# Sheet1.net
KiCad netlist of a schematic drawn in Altium Designer
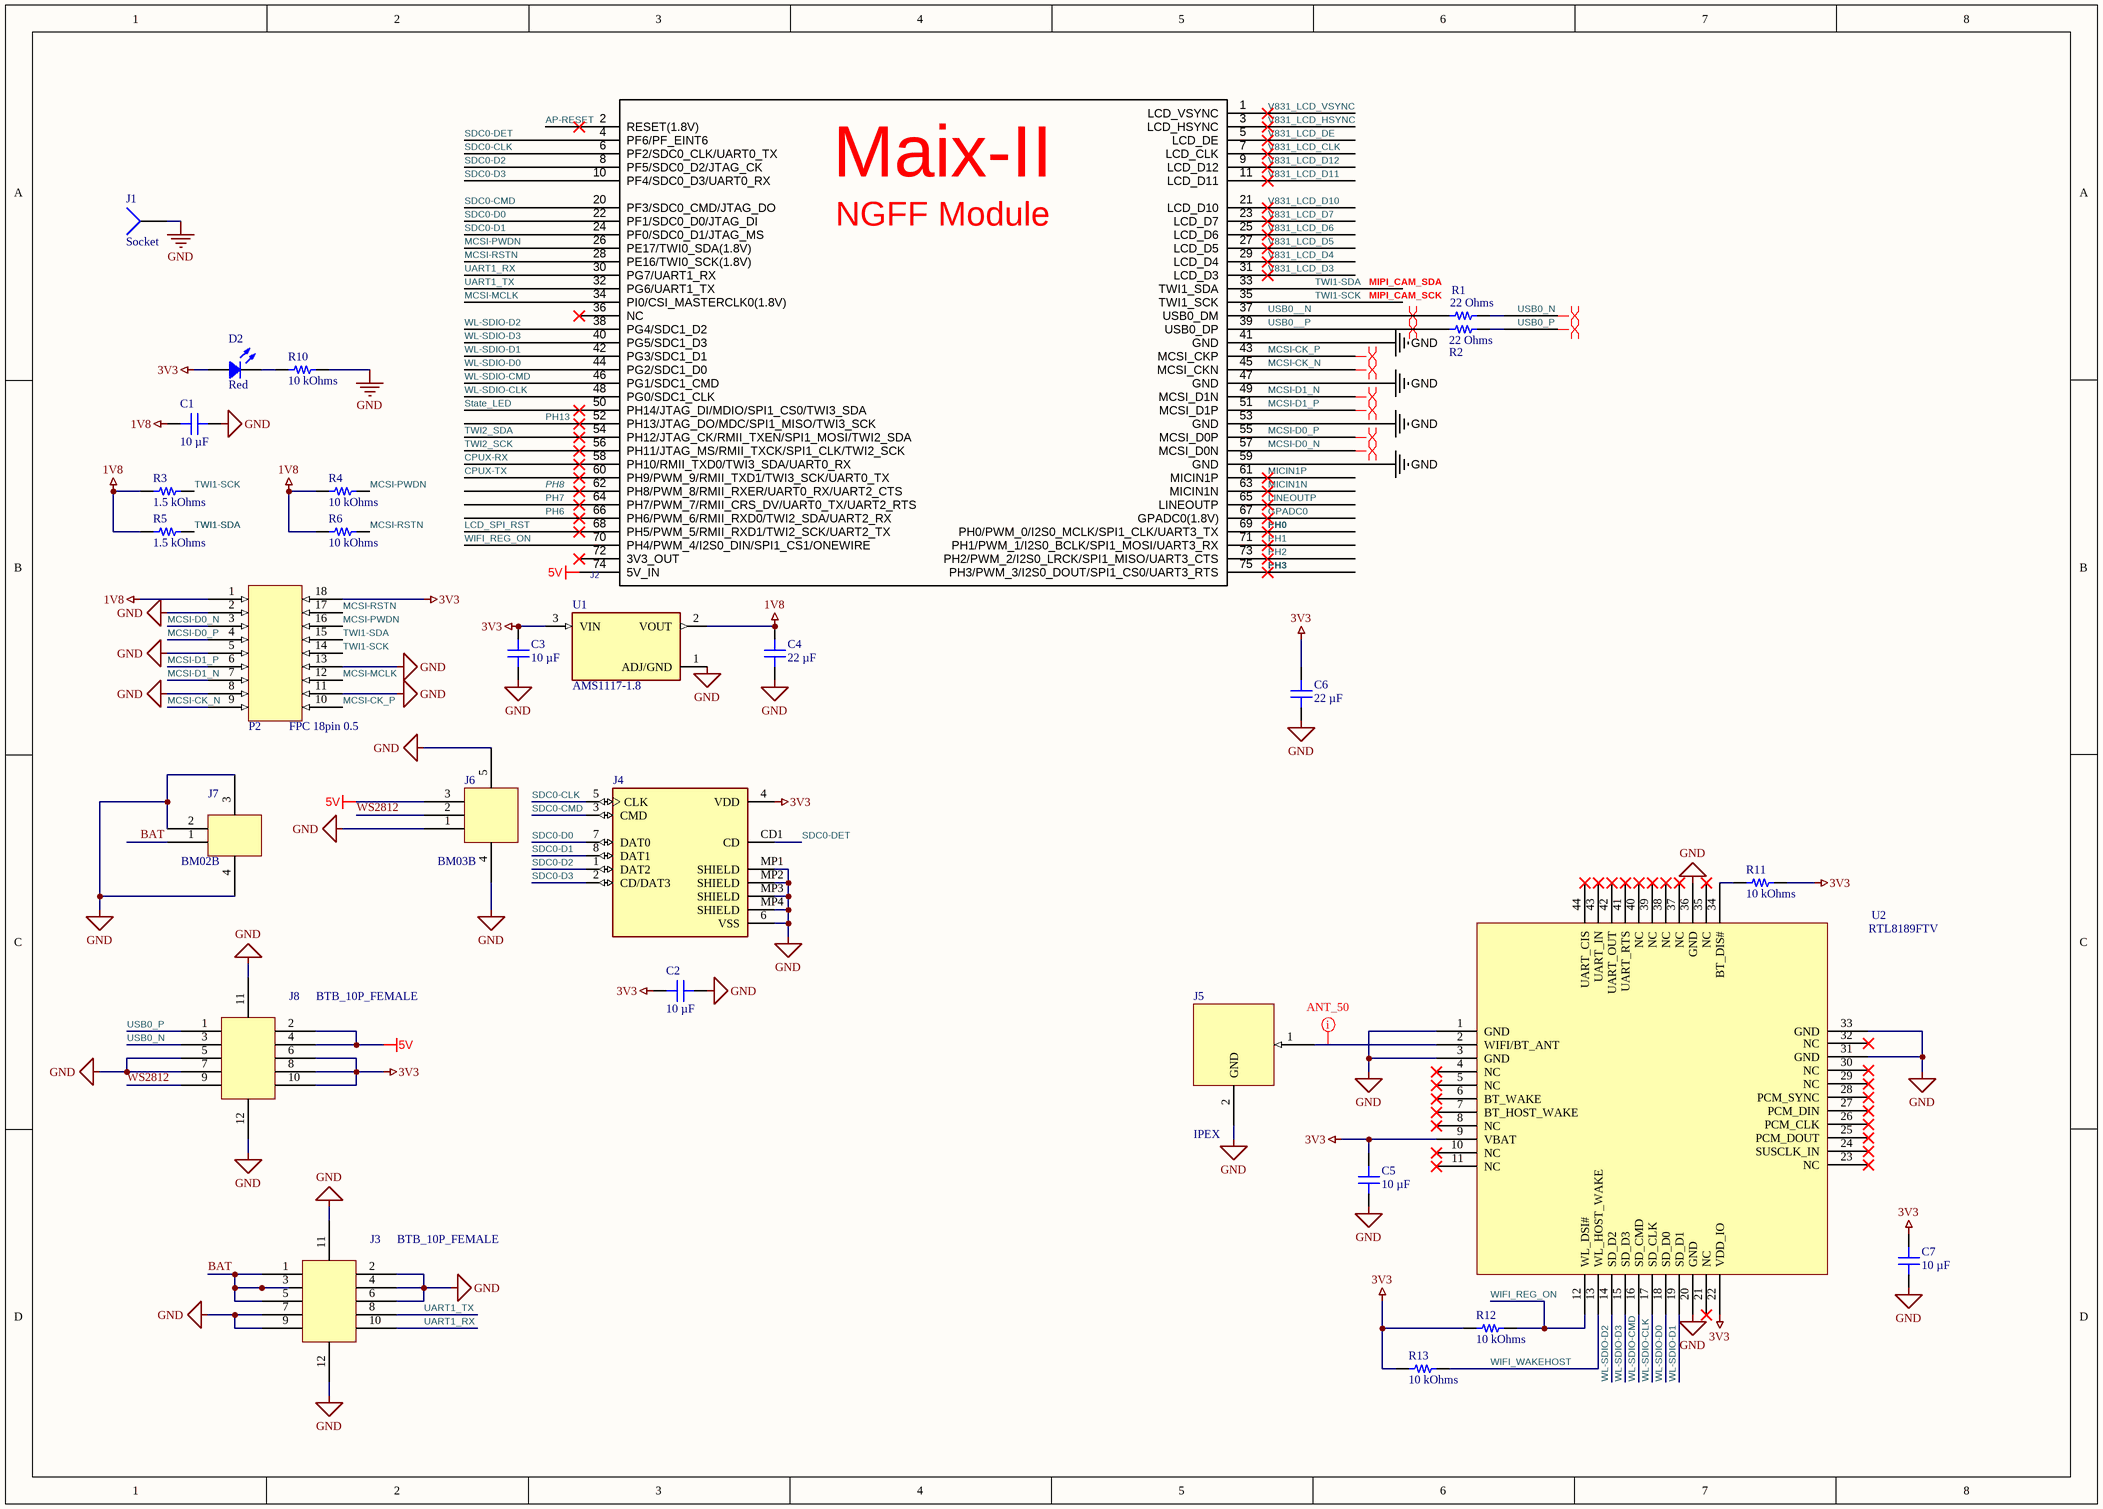
[diagram p0: Sheet1.SchDoc]

(export (version "E")
  (design (tool "Eeschema 10.0.6"))
  (components
    (comp (ref "C1")
      (value "10 µF")
      (footprint "CAP 0402_1005")
      (description "CAP CER 10UF 2.5V X5R 0402")
      (fields
        (field (name "PART NUMBER") "GRM155R60E106ME16D")
        (field (name "MANUFACTURER") "Murata Electronics")
      )
      (libsource (lib "Celestial Altium Library - altium_library") (part "Capacitor"))
    )
    (comp (ref "C2")
      (value "10 µF")
      (footprint "CAP 0402_1005")
      (description "CAP CER 10UF 2.5V X5R 0402")
      (fields
        (field (name "PART NUMBER") "GRM155R60E106ME16D")
        (field (name "MANUFACTURER") "Murata Electronics")
      )
      (libsource (lib "Celestial Altium Library - altium_library") (part "Capacitor"))
    )
    (comp (ref "C3")
      (value "10 µF")
      (footprint "CAP 0402_1005")
      (description "CAP CER 10UF 2.5V X5R 0402")
      (fields
        (field (name "PART NUMBER") "GRM155R60E106ME16D")
        (field (name "MANUFACTURER") "Murata Electronics")
      )
      (libsource (lib "Celestial Altium Library - altium_library") (part "Capacitor"))
    )
    (comp (ref "C4")
      (value "22 µF")
      (footprint "CAP_TAN_A1206")
      (description "CAP CER 10UF 2.5V X5R 0402")
      (fields
        (field (name "PART NUMBER") "GRM155R60E106ME16D")
        (field (name "MANUFACTURER") "Murata Electronics")
      )
      (libsource (lib "Celestial Altium Library - altium_library") (part "Capacitor"))
    )
    (comp (ref "C5")
      (value "10 µF")
      (footprint "CAP 0402_1005")
      (description "CAP CER 10UF 2.5V X5R 0402")
      (fields
        (field (name "PART NUMBER") "GRM155R60E106ME16D")
        (field (name "MANUFACTURER") "Murata Electronics")
      )
      (libsource (lib "Celestial Altium Library - altium_library") (part "Capacitor"))
    )
    (comp (ref "C6")
      (value "22 µF")
      (footprint "CAP_TAN_A1206")
      (description "CAP CER 10UF 2.5V X5R 0402")
      (fields
        (field (name "PART NUMBER") "GRM155R60E106ME16D")
        (field (name "MANUFACTURER") "Murata Electronics")
      )
      (libsource (lib "Celestial Altium Library - altium_library") (part "Capacitor"))
    )
    (comp (ref "C7")
      (value "10 µF")
      (footprint "CAP 0402_1005")
      (description "CAP CER 10UF 2.5V X5R 0402")
      (fields
        (field (name "PART NUMBER") "GRM155R60E106ME16D")
        (field (name "MANUFACTURER") "Murata Electronics")
      )
      (libsource (lib "Celestial Altium Library - altium_library") (part "Capacitor"))
    )
    (comp (ref "D2")
      (value "Red")
      (footprint "LED_0603_RED")
      (description "0402 LED RED, CLEAR LENS, 330MCD")
      (fields (field (name "PART NUMBER") "QBLP595-R-2897") (field (name "MANUFACTURER") "QT Brightek (QTB)"))
      (libsource (lib "Celestial Altium Library - altium_library") (part "LED"))
    )
    (comp (ref "J1")
      (value "Socket")
      (footprint "M.2 SMT-FEMALE - FULL")
      (fields (field (name "PUBLISHER") "Altium Limited"))
      (libsource (lib "Miscellaneous Connectors") (part "Socket"))
    )
    (comp (ref "J2")
      (value "NGFF-67P_B-KEY座子 4.2H高")
      (footprint "M2-67P0R50_B_FEMALE")
      (libsource (lib "V831_Dock_3060") (part "NGFF-67P_B-MALE"))
    )
    (comp (ref "J3")
      (value "BTB_10P_FEMALE")
      (footprint "BTB_10P_FEMALE")
      (libsource (lib "cocube_maix") (part "BTB_10P_FEMALE"))
    )
    (comp (ref "J4")
      (value "TF-01A")
      (footprint "TF-01A")
      (fields (field (name "MF") "{'manufacturer': u'HRO Electronics Co., Ltd.'}"))
      (libsource (lib "SnapEDA_Library") (part "TF-01A"))
    )
    (comp (ref "J5") (value "IPEX") (footprint "IPEX") (libsource (lib "cocube_maix") (part "IPEX")))
    (comp (ref "J6") (value "BM03B") (footprint "BM03B") (libsource (lib "cocube_maix") (part "BM03B")))
    (comp (ref "J7") (value "BM02B") (footprint "BM02B") (libsource (lib "cocube_maix") (part "BM02B")))
    (comp (ref "J8")
      (value "BTB_10P_FEMALE")
      (footprint "BTB_10P_FEMALE")
      (libsource (lib "cocube_maix") (part "BTB_10P_FEMALE"))
    )
    (comp (ref "P2")
      (value "FPC 18pin 0.5")
      (footprint "FPC 18PIN STAND")
      (libsource (lib "maix_2") (part "FPC 18pin 0.5"))
    )
    (comp (ref "R1")
      (value "22 Ohms")
      (footprint "RES 0402_1005")
      (description "RES 22 OHM 1% 1/8W 0402")
      (fields (field (name "PART NUMBER") "SR0402FR-7W22RL") (field (name "MANUFACTURER") "Yageo"))
      (libsource (lib "Celestial Altium Library - altium_library") (part "Resistor"))
    )
    (comp (ref "R2")
      (value "22 Ohms")
      (footprint "RES 0402_1005")
      (description "RES 22 OHM 1% 1/8W 0402")
      (fields (field (name "PART NUMBER") "SR0402FR-7W22RL") (field (name "MANUFACTURER") "Yageo"))
      (libsource (lib "Celestial Altium Library - altium_library") (part "Resistor"))
    )
    (comp (ref "R3")
      (value "1.5 kOhms")
      (footprint "RES 0402_1005")
      (description "PTN0402 10PPM 1.5K 0.1% S T1 E1")
      (fields
        (field (name "PART NUMBER") "PTN0402Y1501BST1")
        (field (name "MANUFACTURER") "Vishay Dale Thin Film")
      )
      (libsource (lib "Celestial Altium Library - altium_library") (part "Resistor"))
    )
    (comp (ref "R4")
      (value "10 kOhms")
      (footprint "RES 0402_1005")
      (description "P2TC0402 2PPM/C 10K 0,01% N TA")
      (fields
        (field (name "PART NUMBER") "P2TC0402D1002LNTA")
        (field (name "MANUFACTURER") "Vishay Sfernice")
      )
      (libsource (lib "Celestial Altium Library - altium_library") (part "Resistor"))
    )
    (comp (ref "R5")
      (value "1.5 kOhms")
      (footprint "RES 0402_1005")
      (description "PTN0402 10PPM 1.5K 0.1% S T1 E1")
      (fields
        (field (name "PART NUMBER") "PTN0402Y1501BST1")
        (field (name "MANUFACTURER") "Vishay Dale Thin Film")
      )
      (libsource (lib "Celestial Altium Library - altium_library") (part "Resistor"))
    )
    (comp (ref "R6")
      (value "10 kOhms")
      (footprint "RES 0402_1005")
      (description "P2TC0402 2PPM/C 10K 0,01% N TA")
      (fields
        (field (name "PART NUMBER") "P2TC0402D1002LNTA")
        (field (name "MANUFACTURER") "Vishay Sfernice")
      )
      (libsource (lib "Celestial Altium Library - altium_library") (part "Resistor"))
    )
    (comp (ref "R10")
      (value "10 kOhms")
      (footprint "RES 0402_1005")
      (description "RES 10K OHM 0.1% 1/10W 0402")
      (fields
        (field (name "PART NUMBER") "RP73PF1E10KBTD")
        (field (name "MANUFACTURER") "TE Connectivity Passive Product")
      )
      (libsource (lib "Celestial Altium Library - altium_library") (part "Resistor"))
    )
    (comp (ref "R11")
      (value "10 kOhms")
      (footprint "RES 0402_1005")
      (description "P2TC0402 2PPM/C 10K 0,01% N TA")
      (fields
        (field (name "PART NUMBER") "P2TC0402D1002LNTA")
        (field (name "MANUFACTURER") "Vishay Sfernice")
      )
      (libsource (lib "Celestial Altium Library - altium_library") (part "Resistor"))
    )
    (comp (ref "R12")
      (value "10 kOhms")
      (footprint "RES 0402_1005")
      (description "P2TC0402 2PPM/C 10K 0,01% N TA")
      (fields
        (field (name "PART NUMBER") "P2TC0402D1002LNTA")
        (field (name "MANUFACTURER") "Vishay Sfernice")
      )
      (libsource (lib "Celestial Altium Library - altium_library") (part "Resistor"))
    )
    (comp (ref "R13")
      (value "10 kOhms")
      (footprint "RES 0402_1005")
      (description "P2TC0402 2PPM/C 10K 0,01% N TA")
      (fields
        (field (name "PART NUMBER") "P2TC0402D1002LNTA")
        (field (name "MANUFACTURER") "Vishay Sfernice")
      )
      (libsource (lib "Celestial Altium Library - altium_library") (part "Resistor"))
    )
    (comp (ref "U1")
      (value "AMS1117-1.8")
      (footprint "SOT89-3")
      (description "Sot223/Pkg 1-Amp 5-Volt Low Drop Out Voltage Regulatator")
      (fields
        (field (name "MP") "AMS1117")
        (field (name "MF") "{'manufacturer': u'Advanced Monolithic Systems'}")
      )
      (libsource (lib "maix_2") (part "AMS1117"))
    )
    (comp (ref "U2")
      (value "RTL8189FTV")
      (footprint "FT89FMST13")
      (libsource (lib "cocube_maix") (part "RTL8189FTV"))
    )
  )
  (nets
    (net (code "1") (name "/AP-RESET") (class "Default")
      (node (ref "J2") (pin "2") (pinfunction "RESET(1.8V)_2") (pintype "passive+no_connect"))
    )
    (net (code "2") (name "/BAT") (class "Default")
      (node (ref "J3") (pin "1") (pintype "passive"))
      (node (ref "J3") (pin "3") (pintype "passive"))
      (node (ref "J3") (pin "5") (pintype "passive"))
      (node (ref "J7") (pin "1") (pintype "passive"))
    )
    (net (code "3") (name "/CPUX-RX") (class "Default")
      (node (ref "J2") (pin "58") (pinfunction "PH10/RMII_TXD0/TWI3_SDA/UART0_RX_58") (pintype "passive+no_connect"))
    )
    (net (code "4") (name "/CPUX-TX") (class "Default")
      (node (ref "J2") (pin "60") (pinfunction "PH9/PWM_9/RMII_TXD1/TWI3_SCK/UART0_TX_60") (pintype "passive+no_connect"))
    )
    (net (code "5") (name "/GPADC0") (class "Default")
      (node (ref "J2") (pin "67") (pinfunction "GPADC0(1.8V)_67") (pintype "passive+no_connect"))
    )
    (net (code "6") (name "/LCD_SPI_RST") (class "Default")
      (node (ref "J2") (pin "68") (pinfunction "PH5/PWM_5/RMII_RXD1/TWI2_SCK/UART2_TX_68") (pintype "passive+no_connect"))
    )
    (net (code "7") (name "/LINEOUTP") (class "Default")
      (node (ref "J2") (pin "65") (pinfunction "LINEOUTP_65") (pintype "passive+no_connect"))
    )
    (net (code "8") (name "/MCSI-CK_N") (class "Default")
      (node (ref "J2") (pin "45") (pinfunction "MCSI_CKN_45") (pintype "passive"))
      (node (ref "P2") (pin "9") (pintype "input"))
    )
    (net (code "9") (name "/MCSI-CK_P") (class "Default")
      (node (ref "J2") (pin "43") (pinfunction "MCSI_CKP_43") (pintype "passive"))
      (node (ref "P2") (pin "10") (pintype "input"))
    )
    (net (code "10") (name "/MCSI-D0_N") (class "Default")
      (node (ref "J2") (pin "57") (pinfunction "MCSI_D0N_57") (pintype "passive"))
      (node (ref "P2") (pin "3") (pintype "input"))
    )
    (net (code "11") (name "/MCSI-D0_P") (class "Default")
      (node (ref "J2") (pin "55") (pinfunction "MCSI_D0P_55") (pintype "passive"))
      (node (ref "P2") (pin "4") (pintype "input"))
    )
    (net (code "12") (name "/MCSI-D1_N") (class "Default")
      (node (ref "J2") (pin "49") (pinfunction "MCSI_D1N_49") (pintype "passive"))
      (node (ref "P2") (pin "7") (pintype "input"))
    )
    (net (code "13") (name "/MCSI-D1_P") (class "Default")
      (node (ref "J2") (pin "51") (pinfunction "MCSI_D1P_51") (pintype "passive"))
      (node (ref "P2") (pin "6") (pintype "input"))
    )
    (net (code "14") (name "/MCSI-MCLK") (class "Default")
      (node (ref "J2") (pin "34") (pinfunction "PI0/CSI_MASTERCLK0(1.8V)_34") (pintype "passive"))
      (node (ref "P2") (pin "12") (pintype "input"))
    )
    (net (code "15") (name "/MCSI-PWDN") (class "Default")
      (node (ref "J2") (pin "26") (pinfunction "PE17/TWI0_SDA(1.8V)_26") (pintype "passive"))
      (node (ref "P2") (pin "16") (pintype "input"))
      (node (ref "R4") (pin "2") (pinfunction "2_2") (pintype "passive"))
    )
    (net (code "16") (name "/MCSI-RSTN") (class "Default")
      (node (ref "J2") (pin "28") (pinfunction "PE16/TWI0_SCK(1.8V)_28") (pintype "passive"))
      (node (ref "P2") (pin "17") (pintype "input"))
      (node (ref "R6") (pin "2") (pinfunction "2_2") (pintype "passive"))
    )
    (net (code "17") (name "/MICIN1N") (class "Default")
      (node (ref "J2") (pin "63") (pinfunction "MICIN1N_63") (pintype "passive+no_connect"))
    )
    (net (code "18") (name "/MICIN1P") (class "Default")
      (node (ref "J2") (pin "61") (pinfunction "MICIN1P_61") (pintype "passive+no_connect"))
    )
    (net (code "19") (name "/PH0") (class "Default")
      (node (ref "J2") (pin "69") (pinfunction "PH0/PWM_0/I2S0_MCLK/SPI1_CLK/UART3_TX_69") (pintype "passive+no_connect"))
    )
    (net (code "20") (name "/PH1") (class "Default")
      (node (ref "J2") (pin "71") (pinfunction "PH1/PWM_1/I2S0_BCLK/SPI1_MOSI/UART3_RX_71") (pintype "passive+no_connect"))
    )
    (net (code "21") (name "/PH2") (class "Default")
      (node (ref "J2") (pin "73") (pinfunction "PH2/PWM_2/I2S0_LRCK/SPI1_MISO/UART3_CTS_73") (pintype "passive+no_connect"))
    )
    (net (code "22") (name "/PH3") (class "Default")
      (node (ref "J2") (pin "75") (pinfunction "PH3/PWM_3/I2S0_DOUT/SPI1_CS0/UART3_RTS_75") (pintype "passive+no_connect"))
    )
    (net (code "23") (name "/PH6") (class "Default")
      (node (ref "J2") (pin "66") (pinfunction "PH6/PWM_6/RMII_RXD0/TWI2_SDA/UART2_RX_66") (pintype "passive+no_connect"))
    )
    (net (code "24") (name "/PH7") (class "Default")
      (node (ref "J2") (pin "64") (pinfunction "PH7/PWM_7/RMII_CRS_DV/UART0_TX/UART2_RTS_64") (pintype "passive+no_connect"))
    )
    (net (code "25") (name "/PH8") (class "Default")
      (node (ref "J2") (pin "62") (pinfunction "PH8/PWM_8/RMII_RXER/UART0_RX/UART2_CTS_62") (pintype "passive+no_connect"))
    )
    (net (code "26") (name "/PH13") (class "Default")
      (node (ref "J2") (pin "52") (pinfunction "PH13/JTAG_DO/MDC/SPI1_MISO/TWI3_SCK_52") (pintype "passive+no_connect"))
    )
    (net (code "27") (name "/SDC0-CLK") (class "Default")
      (node (ref "J2") (pin "6") (pinfunction "PF2/SDC0_CLK/UART0_TX_6") (pintype "passive"))
      (node (ref "J4") (pin "5") (pinfunction "CLK_5") (pintype "bidirectional"))
    )
    (net (code "28") (name "/SDC0-CMD") (class "Default")
      (node (ref "J2") (pin "20") (pinfunction "PF3/SDC0_CMD/JTAG_DO_20") (pintype "passive"))
      (node (ref "J4") (pin "3") (pinfunction "CMD_3") (pintype "bidirectional"))
    )
    (net (code "29") (name "/SDC0-D0") (class "Default")
      (node (ref "J2") (pin "22") (pinfunction "PF1/SDC0_D0/JTAG_DI_22") (pintype "passive"))
      (node (ref "J4") (pin "7") (pinfunction "DAT0_7") (pintype "bidirectional"))
    )
    (net (code "30") (name "/SDC0-D1") (class "Default")
      (node (ref "J2") (pin "24") (pinfunction "PF0/SDC0_D1/JTAG_MS_24") (pintype "passive"))
      (node (ref "J4") (pin "8") (pinfunction "DAT1_8") (pintype "bidirectional"))
    )
    (net (code "31") (name "/SDC0-D2") (class "Default")
      (node (ref "J2") (pin "8") (pinfunction "PF5/SDC0_D2/JTAG_CK_8") (pintype "passive"))
      (node (ref "J4") (pin "1") (pinfunction "DAT2_1") (pintype "bidirectional"))
    )
    (net (code "32") (name "/SDC0-D3") (class "Default")
      (node (ref "J2") (pin "10") (pinfunction "PF4/SDC0_D3/UART0_RX_10") (pintype "passive"))
      (node (ref "J4") (pin "2") (pinfunction "CD/DAT3_2") (pintype "bidirectional"))
    )
    (net (code "33") (name "/SDC0-DET") (class "Default")
      (node (ref "J2") (pin "4") (pinfunction "PF6/PF_EINT6_4") (pintype "passive"))
      (node (ref "J4") (pin "CD1") (pinfunction "CD_CD1") (pintype "passive"))
    )
    (net (code "34") (name "/State_LED") (class "Default")
      (node (ref "J2") (pin "50") (pinfunction "PH14/JTAG_DI/MDIO/SPI1_CS0/TWI3_SDA_50") (pintype "passive+no_connect"))
    )
    (net (code "35") (name "/TWI1-SCK") (class "Default")
      (node (ref "J2") (pin "35") (pinfunction "TWI1_SCK_35") (pintype "passive"))
      (node (ref "P2") (pin "14") (pintype "input"))
      (node (ref "R3") (pin "2") (pinfunction "2_2") (pintype "passive"))
    )
    (net (code "36") (name "/TWI1-SDA") (class "Default")
      (node (ref "J2") (pin "33") (pinfunction "TWI1_SDA_33") (pintype "passive"))
      (node (ref "P2") (pin "15") (pintype "input"))
      (node (ref "R5") (pin "2") (pinfunction "2_2") (pintype "passive"))
    )
    (net (code "37") (name "/TWI2_SCK") (class "Default")
      (node (ref "J2") (pin "56") (pinfunction "PH11/JTAG_MS/RMII_TXCK/SPI1_CLK/TWI2_SCK_56") (pintype "passive+no_connect"))
    )
    (net (code "38") (name "/TWI2_SDA") (class "Default")
      (node (ref "J2") (pin "54") (pinfunction "PH12/JTAG_CK/RMII_TXEN/SPI1_MOSI/TWI2_SDA_54") (pintype "passive+no_connect"))
    )
    (net (code "39") (name "/UART1_RX") (class "Default")
      (node (ref "J2") (pin "30") (pinfunction "PG7/UART1_RX_30") (pintype "passive"))
      (node (ref "J3") (pin "10") (pintype "passive"))
    )
    (net (code "40") (name "/UART1_TX") (class "Default")
      (node (ref "J2") (pin "32") (pinfunction "PG6/UART1_TX_32") (pintype "passive"))
      (node (ref "J3") (pin "8") (pintype "passive"))
    )
    (net (code "41") (name "/USB0_N") (class "Default")
      (node (ref "J8") (pin "3") (pintype "passive"))
      (node (ref "R1") (pin "2") (pinfunction "2_2") (pintype "passive"))
    )
    (net (code "42") (name "/USB0_P") (class "Default")
      (node (ref "J8") (pin "1") (pintype "passive"))
      (node (ref "R2") (pin "2") (pinfunction "2_2") (pintype "passive"))
    )
    (net (code "43") (name "/USB0__N") (class "Default")
      (node (ref "J2") (pin "37") (pinfunction "USB0_DM_37") (pintype "passive"))
      (node (ref "R1") (pin "1") (pinfunction "1_1") (pintype "passive"))
    )
    (net (code "44") (name "/USB0__P") (class "Default")
      (node (ref "J2") (pin "39") (pinfunction "USB0_DP_39") (pintype "passive"))
      (node (ref "R2") (pin "1") (pinfunction "1_1") (pintype "passive"))
    )
    (net (code "45") (name "/V831_LCD_CLK") (class "Default")
      (node (ref "J2") (pin "7") (pinfunction "LCD_CLK_7") (pintype "passive+no_connect"))
    )
    (net (code "46") (name "/V831_LCD_D3") (class "Default")
      (node (ref "J2") (pin "31") (pinfunction "LCD_D3_31") (pintype "passive+no_connect"))
    )
    (net (code "47") (name "/V831_LCD_D4") (class "Default")
      (node (ref "J2") (pin "29") (pinfunction "LCD_D4_29") (pintype "passive+no_connect"))
    )
    (net (code "48") (name "/V831_LCD_D5") (class "Default")
      (node (ref "J2") (pin "27") (pinfunction "LCD_D5_27") (pintype "passive+no_connect"))
    )
    (net (code "49") (name "/V831_LCD_D6") (class "Default")
      (node (ref "J2") (pin "25") (pinfunction "LCD_D6_25") (pintype "passive+no_connect"))
    )
    (net (code "50") (name "/V831_LCD_D7") (class "Default")
      (node (ref "J2") (pin "23") (pinfunction "LCD_D7_23") (pintype "passive+no_connect"))
    )
    (net (code "51") (name "/V831_LCD_D10") (class "Default")
      (node (ref "J2") (pin "21") (pinfunction "LCD_D10_21") (pintype "passive+no_connect"))
    )
    (net (code "52") (name "/V831_LCD_D11") (class "Default")
      (node (ref "J2") (pin "11") (pinfunction "LCD_D11_11") (pintype "passive+no_connect"))
    )
    (net (code "53") (name "/V831_LCD_D12") (class "Default")
      (node (ref "J2") (pin "9") (pinfunction "LCD_D12_9") (pintype "passive+no_connect"))
    )
    (net (code "54") (name "/V831_LCD_DE") (class "Default")
      (node (ref "J2") (pin "5") (pinfunction "LCD_DE_5") (pintype "passive+no_connect"))
    )
    (net (code "55") (name "/V831_LCD_HSYNC") (class "Default")
      (node (ref "J2") (pin "3") (pinfunction "LCD_HSYNC_3") (pintype "passive+no_connect"))
    )
    (net (code "56") (name "/V831_LCD_VSYNC") (class "Default")
      (node (ref "J2") (pin "1") (pinfunction "LCD_VSYNC_1") (pintype "passive+no_connect"))
    )
    (net (code "57") (name "/WIFI_REG_ON") (class "Default")
      (node (ref "J2") (pin "70") (pinfunction "PH4/PWM_4/I2S0_DIN/SPI1_CS1/ONEWIRE_70") (pintype "passive"))
      (node (ref "R12") (pin "2") (pinfunction "2_2") (pintype "passive"))
      (node (ref "U2") (pin "12") (pinfunction "WL_DSI#_12") (pintype "passive"))
    )
    (net (code "58") (name "/WIFI_WAKEHOST") (class "Default")
      (node (ref "R13") (pin "2") (pinfunction "2_2") (pintype "passive"))
      (node (ref "U2") (pin "13") (pinfunction "WL_HOST_WAKE_13") (pintype "passive"))
    )
    (net (code "59") (name "/WL-SDIO-CLK") (class "Default")
      (node (ref "J2") (pin "48") (pinfunction "PG0/SDC1_CLK_48") (pintype "passive"))
      (node (ref "U2") (pin "17") (pinfunction "SD_CLK_17") (pintype "passive"))
    )
    (net (code "60") (name "/WL-SDIO-CMD") (class "Default")
      (node (ref "J2") (pin "46") (pinfunction "PG1/SDC1_CMD_46") (pintype "passive"))
      (node (ref "U2") (pin "16") (pinfunction "SD_CMD_16") (pintype "passive"))
    )
    (net (code "61") (name "/WL-SDIO-D0") (class "Default")
      (node (ref "J2") (pin "44") (pinfunction "PG2/SDC1_D0_44") (pintype "passive"))
      (node (ref "U2") (pin "18") (pinfunction "SD_D0_18") (pintype "passive"))
    )
    (net (code "62") (name "/WL-SDIO-D1") (class "Default")
      (node (ref "J2") (pin "42") (pinfunction "PG3/SDC1_D1_42") (pintype "passive"))
      (node (ref "U2") (pin "19") (pinfunction "SD_D1_19") (pintype "passive"))
    )
    (net (code "63") (name "/WL-SDIO-D2") (class "Default")
      (node (ref "J2") (pin "38") (pinfunction "PG4/SDC1_D2_38") (pintype "passive"))
      (node (ref "U2") (pin "14") (pinfunction "SD_D2_14") (pintype "passive"))
    )
    (net (code "64") (name "/WL-SDIO-D3") (class "Default")
      (node (ref "J2") (pin "40") (pinfunction "PG5/SDC1_D3_40") (pintype "passive"))
      (node (ref "U2") (pin "15") (pinfunction "SD_D3_15") (pintype "passive"))
    )
    (net (code "65") (name "/WS2812") (class "Default")
      (node (ref "J6") (pin "2") (pintype "passive"))
      (node (ref "J8") (pin "9") (pintype "power_in"))
    )
    (net (code "66") (name "1V8") (class "Default")
      (node (ref "C1") (pin "1") (pinfunction "1_1") (pintype "passive"))
      (node (ref "C4") (pin "1") (pinfunction "1_1") (pintype "passive"))
      (node (ref "P2") (pin "1") (pintype "input"))
      (node (ref "R3") (pin "1") (pinfunction "1_1") (pintype "passive"))
      (node (ref "R4") (pin "1") (pinfunction "1_1") (pintype "passive"))
      (node (ref "R5") (pin "1") (pinfunction "1_1") (pintype "passive"))
      (node (ref "R6") (pin "1") (pinfunction "1_1") (pintype "passive"))
      (node (ref "U1") (pin "2") (pinfunction "VOUT_2") (pintype "output"))
    )
    (net (code "67") (name "3V3") (class "Default")
      (node (ref "C2") (pin "1") (pinfunction "1_1") (pintype "passive"))
      (node (ref "C3") (pin "1") (pinfunction "1_1") (pintype "passive"))
      (node (ref "C5") (pin "1") (pinfunction "1_1") (pintype "passive"))
      (node (ref "C6") (pin "1") (pinfunction "1_1") (pintype "passive"))
      (node (ref "C7") (pin "1") (pinfunction "1_1") (pintype "passive"))
      (node (ref "D2") (pin "1") (pinfunction "1_1") (pintype "passive"))
      (node (ref "J4") (pin "4") (pinfunction "VDD_4") (pintype "power_in"))
      (node (ref "J8") (pin "10") (pintype "passive"))
      (node (ref "J8") (pin "6") (pintype "passive"))
      (node (ref "J8") (pin "8") (pintype "passive"))
      (node (ref "P2") (pin "18") (pintype "input"))
      (node (ref "R11") (pin "2") (pinfunction "2_2") (pintype "passive"))
      (node (ref "R12") (pin "1") (pinfunction "1_1") (pintype "passive"))
      (node (ref "R13") (pin "1") (pinfunction "1_1") (pintype "passive"))
      (node (ref "U1") (pin "3") (pinfunction "VIN_3") (pintype "input"))
      (node (ref "U2") (pin "22") (pinfunction "VDD_IO_22") (pintype "passive"))
      (node (ref "U2") (pin "9") (pinfunction "VBAT_9") (pintype "passive"))
    )
    (net (code "68") (name "5V") (class "Default")
      (node (ref "J2") (pin "74") (pinfunction "5V_IN_74") (pintype "passive"))
      (node (ref "J6") (pin "3") (pintype "passive"))
      (node (ref "J8") (pin "2") (pintype "passive"))
      (node (ref "J8") (pin "4") (pintype "passive"))
    )
    (net (code "69") (name "GND") (class "Default")
      (node (ref "C1") (pin "2") (pinfunction "2_2") (pintype "passive"))
      (node (ref "C2") (pin "2") (pinfunction "2_2") (pintype "passive"))
      (node (ref "C3") (pin "2") (pinfunction "2_2") (pintype "passive"))
      (node (ref "C4") (pin "2") (pinfunction "2_2") (pintype "passive"))
      (node (ref "C5") (pin "2") (pinfunction "2_2") (pintype "passive"))
      (node (ref "C6") (pin "2") (pinfunction "2_2") (pintype "passive"))
      (node (ref "C7") (pin "2") (pinfunction "2_2") (pintype "passive"))
      (node (ref "J1") (pin "1") (pinfunction "1_1") (pintype "passive"))
      (node (ref "J2") (pin "41") (pinfunction "GND_41") (pintype "passive"))
      (node (ref "J2") (pin "47") (pinfunction "GND_47") (pintype "passive"))
      (node (ref "J2") (pin "53") (pinfunction "GND_53") (pintype "passive"))
      (node (ref "J2") (pin "59") (pinfunction "GND_59") (pintype "passive"))
      (node (ref "J3") (pin "11") (pinfunction "11_11") (pintype "passive"))
      (node (ref "J3") (pin "12") (pinfunction "12_12") (pintype "passive"))
      (node (ref "J3") (pin "2") (pintype "passive"))
      (node (ref "J3") (pin "4") (pintype "passive"))
      (node (ref "J3") (pin "6") (pintype "passive"))
      (node (ref "J3") (pin "7") (pintype "passive"))
      (node (ref "J3") (pin "9") (pintype "power_in"))
      (node (ref "J4") (pin "6") (pinfunction "VSS_6") (pintype "power_in"))
      (node (ref "J4") (pin "MP1") (pinfunction "SHIELD_MP1") (pintype "power_in"))
      (node (ref "J4") (pin "MP2") (pinfunction "SHIELD_MP2") (pintype "power_in"))
      (node (ref "J4") (pin "MP3") (pinfunction "SHIELD_MP3") (pintype "power_in"))
      (node (ref "J4") (pin "MP4") (pinfunction "SHIELD_MP4") (pintype "power_in"))
      (node (ref "J5") (pin "2") (pinfunction "GND_2") (pintype "passive"))
      (node (ref "J6") (pin "1") (pintype "passive"))
      (node (ref "J6") (pin "4") (pintype "passive"))
      (node (ref "J6") (pin "5") (pintype "passive"))
      (node (ref "J7") (pin "2") (pintype "passive"))
      (node (ref "J7") (pin "3") (pintype "passive"))
      (node (ref "J7") (pin "4") (pintype "passive"))
      (node (ref "J8") (pin "11") (pinfunction "11_11") (pintype "passive"))
      (node (ref "J8") (pin "12") (pinfunction "12_12") (pintype "passive"))
      (node (ref "J8") (pin "5") (pintype "passive"))
      (node (ref "J8") (pin "7") (pintype "passive"))
      (node (ref "P2") (pin "11") (pintype "input"))
      (node (ref "P2") (pin "13") (pintype "input"))
      (node (ref "P2") (pin "2") (pintype "input"))
      (node (ref "P2") (pin "5") (pintype "input"))
      (node (ref "P2") (pin "8") (pintype "input"))
      (node (ref "R10") (pin "2") (pinfunction "2_2") (pintype "passive"))
      (node (ref "U1") (pin "1") (pinfunction "ADJ/GND_1") (pintype "power_in"))
      (node (ref "U2") (pin "1") (pinfunction "GND_1") (pintype "passive"))
      (node (ref "U2") (pin "20") (pinfunction "GND_20") (pintype "passive"))
      (node (ref "U2") (pin "3") (pinfunction "GND_3") (pintype "passive"))
      (node (ref "U2") (pin "31") (pinfunction "GND_31") (pintype "passive"))
      (node (ref "U2") (pin "33") (pinfunction "GND_33") (pintype "passive"))
      (node (ref "U2") (pin "36") (pinfunction "GND_36") (pintype "passive"))
    )
    (net (code "70") (name "Net-(D2-Pad2)") (class "Default")
      (node (ref "D2") (pin "2") (pinfunction "2_2") (pintype "passive"))
      (node (ref "R10") (pin "1") (pinfunction "1_1") (pintype "passive"))
    )
    (net (code "71") (name "Net-(U2-BT_DIS#)") (class "Default")
      (node (ref "R11") (pin "1") (pinfunction "1_1") (pintype "passive"))
      (node (ref "U2") (pin "34") (pinfunction "BT_DIS#_34") (pintype "passive"))
    )
    (net (code "72") (name "Net-(U2-WIFI{slash}BT_ANT)") (class "Default")
      (node (ref "J5") (pin "1") (pintype "input"))
      (node (ref "U2") (pin "2") (pinfunction "WIFI/BT_ANT_2") (pintype "passive"))
    )
    (net (code "73") (name "unconnected-(J2-3V3_OUT-Pad72)") (class "Default")
      (node (ref "J2") (pin "72") (pinfunction "3V3_OUT_72") (pintype "passive+no_connect"))
    )
    (net (code "74") (name "unconnected-(J2-NC-Pad36)") (class "Default")
      (node (ref "J2") (pin "36") (pinfunction "NC_36") (pintype "passive+no_connect"))
    )
    (net (code "75") (name "unconnected-(U2-BT_HOST_WAKE-Pad7)") (class "Default")
      (node (ref "U2") (pin "7") (pinfunction "BT_HOST_WAKE_7") (pintype "passive+no_connect"))
    )
    (net (code "76") (name "unconnected-(U2-BT_WAKE-Pad6)") (class "Default")
      (node (ref "U2") (pin "6") (pinfunction "BT_WAKE_6") (pintype "passive+no_connect"))
    )
    (net (code "77") (name "unconnected-(U2-NC-Pad4)") (class "Default")
      (node (ref "U2") (pin "4") (pinfunction "NC_4") (pintype "passive+no_connect"))
    )
    (net (code "78") (name "unconnected-(U2-NC-Pad5)") (class "Default")
      (node (ref "U2") (pin "5") (pinfunction "NC_5") (pintype "passive+no_connect"))
    )
    (net (code "79") (name "unconnected-(U2-NC-Pad8)") (class "Default")
      (node (ref "U2") (pin "8") (pinfunction "NC_8") (pintype "passive+no_connect"))
    )
    (net (code "80") (name "unconnected-(U2-NC-Pad10)") (class "Default")
      (node (ref "U2") (pin "10") (pinfunction "NC_10") (pintype "passive+no_connect"))
    )
    (net (code "81") (name "unconnected-(U2-NC-Pad11)") (class "Default")
      (node (ref "U2") (pin "11") (pinfunction "NC_11") (pintype "passive+no_connect"))
    )
    (net (code "82") (name "unconnected-(U2-NC-Pad21)") (class "Default")
      (node (ref "U2") (pin "21") (pinfunction "NC_21") (pintype "passive+no_connect"))
    )
    (net (code "83") (name "unconnected-(U2-NC-Pad23)") (class "Default")
      (node (ref "U2") (pin "23") (pinfunction "NC_23") (pintype "passive+no_connect"))
    )
    (net (code "84") (name "unconnected-(U2-NC-Pad29)") (class "Default")
      (node (ref "U2") (pin "29") (pinfunction "NC_29") (pintype "passive+no_connect"))
    )
    (net (code "85") (name "unconnected-(U2-NC-Pad30)") (class "Default")
      (node (ref "U2") (pin "30") (pinfunction "NC_30") (pintype "passive+no_connect"))
    )
    (net (code "86") (name "unconnected-(U2-NC-Pad32)") (class "Default")
      (node (ref "U2") (pin "32") (pinfunction "NC_32") (pintype "passive+no_connect"))
    )
    (net (code "87") (name "unconnected-(U2-NC-Pad35)") (class "Default")
      (node (ref "U2") (pin "35") (pinfunction "NC_35") (pintype "passive+no_connect"))
    )
    (net (code "88") (name "unconnected-(U2-NC-Pad37)") (class "Default")
      (node (ref "U2") (pin "37") (pinfunction "NC_37") (pintype "passive+no_connect"))
    )
    (net (code "89") (name "unconnected-(U2-NC-Pad38)") (class "Default")
      (node (ref "U2") (pin "38") (pinfunction "NC_38") (pintype "passive+no_connect"))
    )
    (net (code "90") (name "unconnected-(U2-NC-Pad39)") (class "Default")
      (node (ref "U2") (pin "39") (pinfunction "NC_39") (pintype "passive+no_connect"))
    )
    (net (code "91") (name "unconnected-(U2-NC-Pad40)") (class "Default")
      (node (ref "U2") (pin "40") (pinfunction "NC_40") (pintype "passive+no_connect"))
    )
    (net (code "92") (name "unconnected-(U2-PCM_CLK-Pad26)") (class "Default")
      (node (ref "U2") (pin "26") (pinfunction "PCM_CLK_26") (pintype "passive+no_connect"))
    )
    (net (code "93") (name "unconnected-(U2-PCM_DIN-Pad27)") (class "Default")
      (node (ref "U2") (pin "27") (pinfunction "PCM_DIN_27") (pintype "passive+no_connect"))
    )
    (net (code "94") (name "unconnected-(U2-PCM_DOUT-Pad25)") (class "Default")
      (node (ref "U2") (pin "25") (pinfunction "PCM_DOUT_25") (pintype "passive+no_connect"))
    )
    (net (code "95") (name "unconnected-(U2-PCM_SYNC-Pad28)") (class "Default")
      (node (ref "U2") (pin "28") (pinfunction "PCM_SYNC_28") (pintype "passive+no_connect"))
    )
    (net (code "96") (name "unconnected-(U2-SUSCLK_IN-Pad24)") (class "Default")
      (node (ref "U2") (pin "24") (pinfunction "SUSCLK_IN_24") (pintype "passive+no_connect"))
    )
    (net (code "97") (name "unconnected-(U2-UART_CIS-Pad44)") (class "Default")
      (node (ref "U2") (pin "44") (pinfunction "UART_CIS_44") (pintype "passive+no_connect"))
    )
    (net (code "98") (name "unconnected-(U2-UART_IN-Pad43)") (class "Default")
      (node (ref "U2") (pin "43") (pinfunction "UART_IN_43") (pintype "passive+no_connect"))
    )
    (net (code "99") (name "unconnected-(U2-UART_OUT-Pad42)") (class "Default")
      (node (ref "U2") (pin "42") (pinfunction "UART_OUT_42") (pintype "passive+no_connect"))
    )
    (net (code "100") (name "unconnected-(U2-UART_RTS-Pad41)") (class "Default")
      (node (ref "U2") (pin "41") (pinfunction "UART_RTS_41") (pintype "passive+no_connect"))
    )
  )
)
